# USB_OTG_FS.net
KiCad netlist of a schematic drawn in Altium Designer
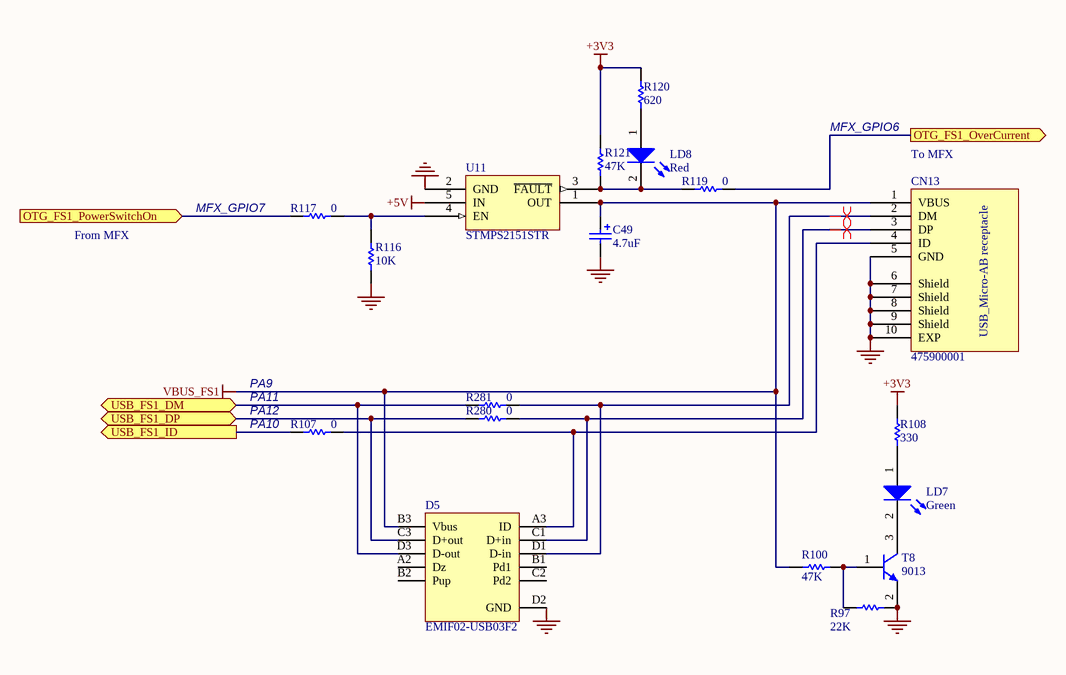
[diagram p0: USB_OTG_FS.SchDoc]

(export (version "E")
  (design (tool "Eeschema 10.0.6"))
  (components
    (comp (ref "C49")
      (value "4.7uF")
      (footprint "TAN-A")
      (description "Polarized Capacitor (Radial)")
      (fields (field (name "PUBLISHER") "Altium Limited"))
      (libsource (lib "Miscellaneous Devices") (part "Cap Pol1"))
    )
    (comp (ref "CN13")
      (value "475900001")
      (footprint "MOLEX_47590001")
      (libsource (lib "mb1045") (part "475900001"))
    )
    (comp (ref "D5")
      (value "EMIF02-USB03F2")
      (footprint "BGA11_0R5_1R57X2R07")
      (libsource (lib "mb1045") (part "EMIF02-USB03F2"))
    )
    (comp (ref "LD7")
      (value "Green")
      (footprint "0603D")
      (description "Typical RED, GREEN, YELLOW, AMBER GaAs LED")
      (fields (field (name "PUBLISHER") "Altium Limited"))
      (libsource (lib "Miscellaneous Devices") (part "LED2"))
    )
    (comp (ref "LD8")
      (value "Red")
      (footprint "0603D")
      (description "Typical RED, GREEN, YELLOW, AMBER GaAs LED")
      (fields (field (name "PUBLISHER") "Altium Limited"))
      (libsource (lib "Miscellaneous Devices") (part "LED2"))
    )
    (comp (ref "R97")
      (value "22K")
      (footprint "0603R")
      (description "Resistor")
      (fields (field (name "PUBLISHER") "Altium Limited"))
      (libsource (lib "Miscellaneous Devices") (part "res1"))
    )
    (comp (ref "R100")
      (value "47K")
      (footprint "0603R")
      (description "Resistor")
      (fields (field (name "PUBLISHER") "Altium Limited"))
      (libsource (lib "Miscellaneous Devices") (part "res1"))
    )
    (comp (ref "R107")
      (value "0")
      (footprint "0603R")
      (description "Resistor")
      (fields (field (name "PUBLISHER") "Altium Limited"))
      (libsource (lib "Miscellaneous Devices") (part "Res1"))
    )
    (comp (ref "R108")
      (value "330")
      (footprint "0603R")
      (description "Resistor")
      (fields (field (name "PUBLISHER") "Altium Limited"))
      (libsource (lib "Miscellaneous Devices") (part "res1"))
    )
    (comp (ref "R116")
      (value "10K")
      (footprint "0603R")
      (description "Resistor")
      (fields (field (name "PUBLISHER") "Altium Limited"))
      (libsource (lib "Miscellaneous Devices") (part "Res1"))
    )
    (comp (ref "R117")
      (value "0")
      (footprint "0603R")
      (description "Resistor")
      (fields (field (name "PUBLISHER") "Altium Limited"))
      (libsource (lib "Miscellaneous Devices") (part "Res1"))
    )
    (comp (ref "R119")
      (value "0")
      (footprint "0603R")
      (description "Resistor")
      (fields (field (name "PUBLISHER") "Altium Limited"))
      (libsource (lib "Miscellaneous Devices") (part "Res1"))
    )
    (comp (ref "R120")
      (value "620")
      (footprint "0603R")
      (description "Resistor")
      (fields (field (name "PUBLISHER") "Altium Limited"))
      (libsource (lib "Miscellaneous Devices") (part "Res1"))
    )
    (comp (ref "R121")
      (value "47K")
      (footprint "0603R")
      (description "Resistor")
      (fields (field (name "PUBLISHER") "Altium Limited"))
      (libsource (lib "Miscellaneous Devices") (part "res1"))
    )
    (comp (ref "R280")
      (value "0")
      (footprint "0603R")
      (description "Resistor")
      (fields (field (name "PUBLISHER") "Altium Limited"))
      (libsource (lib "Miscellaneous Devices") (part "Res1"))
    )
    (comp (ref "R281")
      (value "0")
      (footprint "0603R")
      (description "Resistor")
      (fields (field (name "PUBLISHER") "Altium Limited"))
      (libsource (lib "Miscellaneous Devices") (part "Res1"))
    )
    (comp (ref "T8")
      (value "9013")
      (footprint "SOT-23")
      (description "NPN Bipolar Transistor")
      (fields (field (name "PUBLISHER") "Altium Limited"))
      (libsource (lib "MB1167") (part "NPN"))
    )
    (comp (ref "U11")
      (value "STMPS2151STR")
      (footprint "SOT23-5")
      (libsource (lib "mb1045") (part "STMPS2141STR"))
    )
  )
  (nets
    (net (code "1") (name "+3V3") (class "Default")
      (node (ref "R108") (pin "2") (pinfunction "2_2") (pintype "passive"))
      (node (ref "R120") (pin "2") (pinfunction "2_2") (pintype "passive"))
      (node (ref "R121") (pin "1") (pinfunction "1_1") (pintype "passive"))
    )
    (net (code "2") (name "+5V") (class "Default")
      (node (ref "U11") (pin "5") (pinfunction "IN_5") (pintype "passive"))
    )
    (net (code "3") (name "/OTG_FS1_OverCurrent") (class "Default")
      (node (ref "R119") (pin "1") (pinfunction "1_1") (pintype "passive"))
    )
    (net (code "4") (name "/OTG_FS1_PowerSwitchOn") (class "Default")
      (node (ref "R117") (pin "2") (pinfunction "2_2") (pintype "passive"))
    )
    (net (code "5") (name "/USB_FS1_DM") (class "Default")
      (node (ref "D5") (pin "D3") (pinfunction "D-out_D3") (pintype "passive"))
      (node (ref "R281") (pin "2") (pinfunction "2_2") (pintype "passive"))
    )
    (net (code "6") (name "/USB_FS1_DP") (class "Default")
      (node (ref "D5") (pin "C3") (pinfunction "D+out_C3") (pintype "passive"))
      (node (ref "R280") (pin "2") (pinfunction "2_2") (pintype "passive"))
    )
    (net (code "7") (name "/USB_FS1_ID") (class "Default")
      (node (ref "R107") (pin "2") (pinfunction "2_2") (pintype "passive"))
    )
    (net (code "8") (name "GND") (class "Default")
      (node (ref "C49") (pin "2") (pinfunction "2_2") (pintype "passive"))
      (node (ref "CN13") (pin "10") (pinfunction "EXP_10") (pintype "passive"))
      (node (ref "CN13") (pin "5") (pinfunction "GND_5") (pintype "passive"))
      (node (ref "CN13") (pin "6") (pinfunction "Shield_6") (pintype "passive"))
      (node (ref "CN13") (pin "7") (pinfunction "Shield_7") (pintype "passive"))
      (node (ref "CN13") (pin "8") (pinfunction "Shield_8") (pintype "passive"))
      (node (ref "CN13") (pin "9") (pinfunction "Shield_9") (pintype "passive"))
      (node (ref "D5") (pin "D2") (pinfunction "GND_D2") (pintype "passive"))
      (node (ref "R116") (pin "1") (pinfunction "1_1") (pintype "passive"))
      (node (ref "R97") (pin "1") (pinfunction "1_1") (pintype "passive"))
      (node (ref "T8") (pin "2") (pinfunction "E_2") (pintype "passive"))
      (node (ref "U11") (pin "2") (pinfunction "GND_2") (pintype "passive"))
    )
    (net (code "9") (name "Net-(CN13-DM)") (class "Default")
      (node (ref "CN13") (pin "2") (pinfunction "DM_2") (pintype "passive"))
      (node (ref "D5") (pin "D1") (pinfunction "D-in_D1") (pintype "passive"))
      (node (ref "R281") (pin "1") (pinfunction "1_1") (pintype "passive"))
    )
    (net (code "10") (name "Net-(CN13-DP)") (class "Default")
      (node (ref "CN13") (pin "3") (pinfunction "DP_3") (pintype "passive"))
      (node (ref "D5") (pin "C1") (pinfunction "D+in_C1") (pintype "passive"))
      (node (ref "R280") (pin "1") (pinfunction "1_1") (pintype "passive"))
    )
    (net (code "11") (name "Net-(CN13-ID)") (class "Default")
      (node (ref "CN13") (pin "4") (pinfunction "ID_4") (pintype "passive"))
      (node (ref "D5") (pin "A3") (pinfunction "ID_A3") (pintype "passive"))
      (node (ref "R107") (pin "1") (pinfunction "1_1") (pintype "passive"))
    )
    (net (code "12") (name "Net-(LD7-A)") (class "Default")
      (node (ref "LD7") (pin "1") (pinfunction "A_1") (pintype "passive"))
      (node (ref "R108") (pin "1") (pinfunction "1_1") (pintype "passive"))
    )
    (net (code "13") (name "Net-(LD7-K)") (class "Default")
      (node (ref "LD7") (pin "2") (pinfunction "K_2") (pintype "passive"))
      (node (ref "T8") (pin "3") (pinfunction "C_3") (pintype "passive"))
    )
    (net (code "14") (name "Net-(LD8-A)") (class "Default")
      (node (ref "LD8") (pin "1") (pinfunction "A_1") (pintype "passive"))
      (node (ref "R120") (pin "1") (pinfunction "1_1") (pintype "passive"))
    )
    (net (code "15") (name "Net-(LD8-K)") (class "Default")
      (node (ref "LD8") (pin "2") (pinfunction "K_2") (pintype "passive"))
      (node (ref "R119") (pin "2") (pinfunction "2_2") (pintype "passive"))
      (node (ref "R121") (pin "2") (pinfunction "2_2") (pintype "passive"))
      (node (ref "U11") (pin "3") (pinfunction "~{FAULT}_3") (pintype "output"))
    )
    (net (code "16") (name "Net-(T8-B)") (class "Default")
      (node (ref "R100") (pin "2") (pinfunction "2_2") (pintype "passive"))
      (node (ref "R97") (pin "2") (pinfunction "2_2") (pintype "passive"))
      (node (ref "T8") (pin "1") (pinfunction "B_1") (pintype "passive"))
    )
    (net (code "17") (name "Net-(U11-EN)") (class "Default")
      (node (ref "R116") (pin "2") (pinfunction "2_2") (pintype "passive"))
      (node (ref "R117") (pin "1") (pinfunction "1_1") (pintype "passive"))
      (node (ref "U11") (pin "4") (pinfunction "EN_4") (pintype "input"))
    )
    (net (code "18") (name "VBUS_FS1") (class "Default")
      (node (ref "C49") (pin "1") (pinfunction "1_1") (pintype "passive"))
      (node (ref "CN13") (pin "1") (pinfunction "VBUS_1") (pintype "passive"))
      (node (ref "D5") (pin "B3") (pinfunction "Vbus_B3") (pintype "passive"))
      (node (ref "R100") (pin "1") (pinfunction "1_1") (pintype "passive"))
      (node (ref "U11") (pin "1") (pinfunction "OUT_1") (pintype "passive"))
    )
    (net (code "19") (name "unconnected-(D5-Dz-PadA2)") (class "Default")
      (node (ref "D5") (pin "A2") (pinfunction "Dz_A2") (pintype "passive"))
    )
    (net (code "20") (name "unconnected-(D5-Pd1-PadB1)") (class "Default")
      (node (ref "D5") (pin "B1") (pinfunction "Pd1_B1") (pintype "passive"))
    )
    (net (code "21") (name "unconnected-(D5-Pd2-PadC2)") (class "Default")
      (node (ref "D5") (pin "C2") (pinfunction "Pd2_C2") (pintype "passive"))
    )
    (net (code "22") (name "unconnected-(D5-Pup-PadB2)") (class "Default")
      (node (ref "D5") (pin "B2") (pinfunction "Pup_B2") (pintype "passive"))
    )
  )
)
